# MainBoardR3.net
KiCad netlist of a schematic drawn in EAGLE
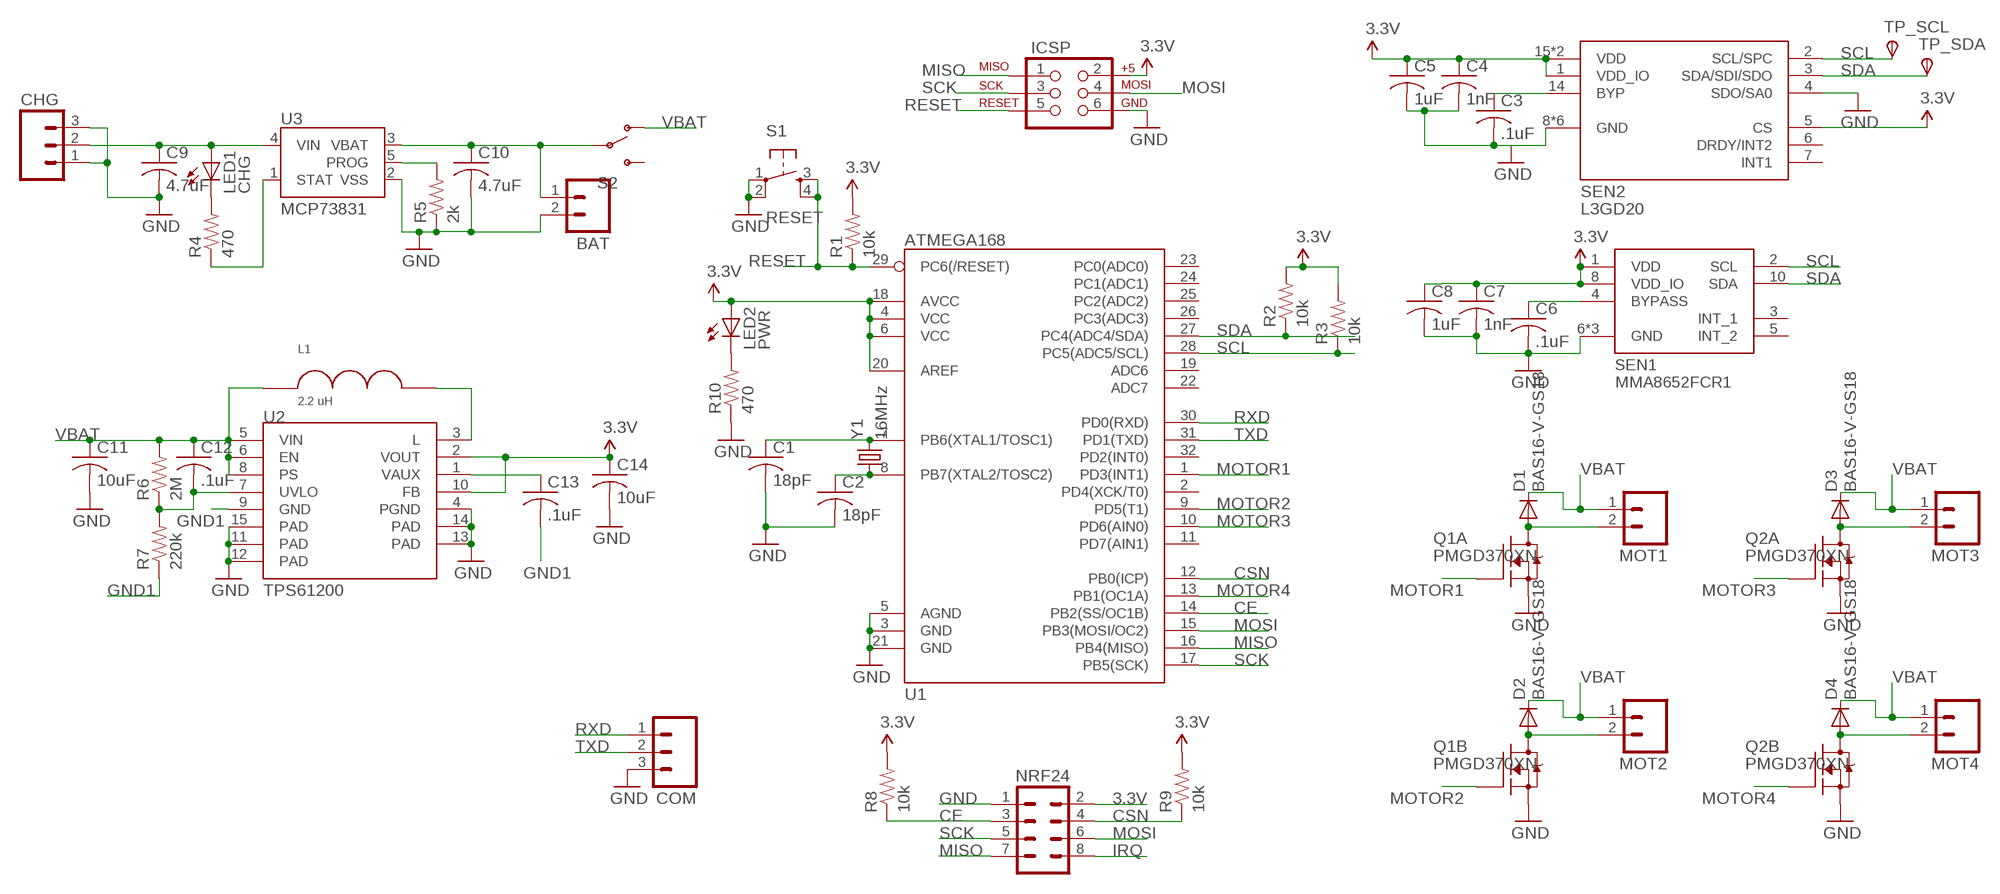
[diagram p0: schematic, sheet 1]

(export (version "E")
  (design (tool "Eeschema 10.0.6"))
  (components
    (comp (ref "BAT")
      (value "M02LOCK_LONGPADS")
      (footprint "eagle-import:1X02_LOCK_LONGPADS")
      (libsource (lib "eagle-import") (part "M02LOCK_LONGPADS"))
    )
    (comp (ref "C1")
      (value "18pF")
      (footprint "eagle-import:C0805")
      (libsource (lib "eagle-import") (part "C-USC0805"))
    )
    (comp (ref "C2")
      (value "18pF")
      (footprint "eagle-import:C0805")
      (libsource (lib "eagle-import") (part "C-USC0805"))
    )
    (comp (ref "C3")
      (value ".1uF")
      (footprint "eagle-import:C0805")
      (libsource (lib "eagle-import") (part "C-USC0805"))
    )
    (comp (ref "C4")
      (value "1nF")
      (footprint "eagle-import:C0805")
      (libsource (lib "eagle-import") (part "C-USC0805"))
    )
    (comp (ref "C5")
      (value "1uF")
      (footprint "eagle-import:C0805")
      (libsource (lib "eagle-import") (part "C-USC0805"))
    )
    (comp (ref "C6")
      (value ".1uF")
      (footprint "eagle-import:C0805")
      (libsource (lib "eagle-import") (part "C-USC0805"))
    )
    (comp (ref "C7")
      (value "1nF")
      (footprint "eagle-import:C0805")
      (libsource (lib "eagle-import") (part "C-USC0805"))
    )
    (comp (ref "C8")
      (value "1uF")
      (footprint "eagle-import:C0805")
      (libsource (lib "eagle-import") (part "C-USC0805"))
    )
    (comp (ref "C9")
      (value "4.7uF")
      (footprint "eagle-import:C0805")
      (libsource (lib "eagle-import") (part "C-USC0805"))
    )
    (comp (ref "C10")
      (value "4.7uF")
      (footprint "eagle-import:C0805")
      (libsource (lib "eagle-import") (part "C-USC0805"))
    )
    (comp (ref "C11")
      (value "10uF")
      (footprint "eagle-import:C0805")
      (libsource (lib "eagle-import") (part "C-USC0805"))
    )
    (comp (ref "C12")
      (value ".1uF")
      (footprint "eagle-import:C0805")
      (libsource (lib "eagle-import") (part "C-USC0805"))
    )
    (comp (ref "C13")
      (value ".1uF")
      (footprint "eagle-import:C0805")
      (libsource (lib "eagle-import") (part "C-USC0805"))
    )
    (comp (ref "C14")
      (value "10uF")
      (footprint "eagle-import:C0805")
      (libsource (lib "eagle-import") (part "C-USC0805"))
    )
    (comp (ref "CHG")
      (value "M03LONGPADS")
      (footprint "eagle-import:1X03_LONGPADS")
      (libsource (lib "eagle-import") (part "M03LONGPADS"))
    )
    (comp (ref "COM")
      (value "M03LONGPADS")
      (footprint "eagle-import:1X03_LONGPADS")
      (libsource (lib "eagle-import") (part "M03LONGPADS"))
    )
    (comp (ref "D1")
      (value "BAS16-V-GS18")
      (footprint "eagle-import:SOT23")
      (libsource (lib "eagle-import") (part "BAS16-V-GS18"))
    )
    (comp (ref "D2")
      (value "BAS16-V-GS18")
      (footprint "eagle-import:SOT23")
      (libsource (lib "eagle-import") (part "BAS16-V-GS18"))
    )
    (comp (ref "D3")
      (value "BAS16-V-GS18")
      (footprint "eagle-import:SOT23")
      (libsource (lib "eagle-import") (part "BAS16-V-GS18"))
    )
    (comp (ref "D4")
      (value "BAS16-V-GS18")
      (footprint "eagle-import:SOT23")
      (libsource (lib "eagle-import") (part "BAS16-V-GS18"))
    )
    (comp (ref "ICSP")
      (value "AVR_SPI_PRG_62X3_LOCK")
      (footprint "eagle-import:2X3_LOCK")
      (libsource (lib "eagle-import") (part "AVR_SPI_PRG_62X3_LOCK"))
    )
    (comp (ref "L1")
      (value "2.2 uH")
      (footprint "eagle-import:2518")
      (libsource (lib "eagle-import") (part "BRHL2518T2R2M"))
    )
    (comp (ref "LED1")
      (value "CHG")
      (footprint "eagle-import:LED-1206")
      (libsource (lib "eagle-import") (part "LED1206"))
    )
    (comp (ref "LED2")
      (value "PWR")
      (footprint "eagle-import:LED-1206")
      (libsource (lib "eagle-import") (part "LED1206"))
    )
    (comp (ref "MOT1")
      (value "M02LOCK_LONGPADS")
      (footprint "eagle-import:1X02_LOCK_LONGPADS")
      (libsource (lib "eagle-import") (part "M02LOCK_LONGPADS"))
    )
    (comp (ref "MOT2")
      (value "M02LOCK_LONGPADS")
      (footprint "eagle-import:1X02_LOCK_LONGPADS")
      (libsource (lib "eagle-import") (part "M02LOCK_LONGPADS"))
    )
    (comp (ref "MOT3")
      (value "M02LOCK_LONGPADS")
      (footprint "eagle-import:1X02_LOCK_LONGPADS")
      (libsource (lib "eagle-import") (part "M02LOCK_LONGPADS"))
    )
    (comp (ref "MOT4")
      (value "M02LOCK_LONGPADS")
      (footprint "eagle-import:1X02_LOCK_LONGPADS")
      (libsource (lib "eagle-import") (part "M02LOCK_LONGPADS"))
    )
    (comp (ref "NRF24")
      (value "M04X2")
      (footprint "eagle-import:2X4")
      (libsource (lib "eagle-import") (part "M04X2"))
    )
    (comp (ref "Q1")
      (value "PMGD370XN")
      (footprint "eagle-import:SOT363_INFINEON")
      (libsource (lib "eagle-import") (part "PMGD370XN"))
    )
    (comp (ref "Q2")
      (value "PMGD370XN")
      (footprint "eagle-import:SOT363_INFINEON")
      (libsource (lib "eagle-import") (part "PMGD370XN"))
    )
    (comp (ref "R1")
      (value "10k")
      (footprint "eagle-import:0805")
      (libsource (lib "eagle-import") (part "RESISTOR0805-RES"))
    )
    (comp (ref "R2")
      (value "10k")
      (footprint "eagle-import:0805")
      (libsource (lib "eagle-import") (part "RESISTOR0805-RES"))
    )
    (comp (ref "R3")
      (value "10k")
      (footprint "eagle-import:0805")
      (libsource (lib "eagle-import") (part "RESISTOR0805-RES"))
    )
    (comp (ref "R4")
      (value "470")
      (footprint "eagle-import:0805")
      (libsource (lib "eagle-import") (part "RESISTOR0805-RES"))
    )
    (comp (ref "R5")
      (value "2k")
      (footprint "eagle-import:0805")
      (libsource (lib "eagle-import") (part "RESISTOR0805-RES"))
    )
    (comp (ref "R6")
      (value "2M")
      (footprint "eagle-import:0805")
      (libsource (lib "eagle-import") (part "RESISTOR0805-RES"))
    )
    (comp (ref "R7")
      (value "220k")
      (footprint "eagle-import:0805")
      (libsource (lib "eagle-import") (part "RESISTOR0805-RES"))
    )
    (comp (ref "R8")
      (value "10k")
      (footprint "eagle-import:0805")
      (libsource (lib "eagle-import") (part "RESISTOR0805-RES"))
    )
    (comp (ref "R9")
      (value "10k")
      (footprint "eagle-import:0805")
      (libsource (lib "eagle-import") (part "RESISTOR0805-RES"))
    )
    (comp (ref "R10")
      (value "470")
      (footprint "eagle-import:0805")
      (libsource (lib "eagle-import") (part "RESISTOR0805-RES"))
    )
    (comp (ref "S1")
      (value "RESET")
      (footprint "eagle-import:TACTILE_SWITCH_SMD")
      (libsource (lib "eagle-import") (part "TAC_SWITCHSMD"))
    )
    (comp (ref "S2")
      (value "SWITCH-SPST-SMD-A")
      (footprint "eagle-import:SWITCH-SPST-SMD-A")
      (libsource (lib "eagle-import") (part "SWITCH-SPST-SMD-A"))
    )
    (comp (ref "SEN1")
      (value "MMA8652FCR1")
      (footprint "eagle-import:10_PIN_DFN")
      (libsource (lib "eagle-import") (part "MMA8652FCR1"))
    )
    (comp (ref "SEN2")
      (value "L3GD20")
      (footprint "eagle-import:LGA-16")
      (libsource (lib "eagle-import") (part "L3GD20"))
    )
    (comp (ref "TP_SCL")
      (value "TPSTP14SQ")
      (footprint "eagle-import:TP14SQ")
      (libsource (lib "eagle-import") (part "TPSTP14SQ"))
    )
    (comp (ref "TP_SDA")
      (value "TPSTP14SQ")
      (footprint "eagle-import:TP14SQ")
      (libsource (lib "eagle-import") (part "TPSTP14SQ"))
    )
    (comp (ref "U1")
      (value "ATMEGA168")
      (footprint "eagle-import:TQFP32-08")
      (libsource (lib "eagle-import") (part "ATMEGA168"))
    )
    (comp (ref "U2")
      (value "TPS61200")
      (footprint "eagle-import:QFN-10_PAD")
      (libsource (lib "eagle-import") (part "TPS61200"))
    )
    (comp (ref "U3")
      (value "MCP73831")
      (footprint "eagle-import:SOT23-5")
      (libsource (lib "eagle-import") (part "MCP73831"))
    )
    (comp (ref "Y1")
      (value "16MHz")
      (footprint "eagle-import:CRYSTAL-SMD-10.5X4.8-2PIN")
      (libsource (lib "eagle-import") (part "CRYSTAL10.5X4.8"))
    )
  )
  (nets
    (net (code "1") (name "/CE") (class "Default")
      (node (ref "NRF24") (pin "3") (pinfunction "3_3") (pintype "passive"))
      (node (ref "R8") (pin "1") (pinfunction "1_1") (pintype "passive"))
      (node (ref "U1") (pin "14") (pinfunction "PB2(SS/OC1B)_14") (pintype "bidirectional"))
    )
    (net (code "2") (name "/CSN") (class "Default")
      (node (ref "NRF24") (pin "4") (pinfunction "4_4") (pintype "passive"))
      (node (ref "R9") (pin "1") (pinfunction "1_1") (pintype "passive"))
      (node (ref "U1") (pin "12") (pinfunction "PB0(ICP)_12") (pintype "bidirectional"))
    )
    (net (code "3") (name "/GND1") (class "Default")
      (node (ref "C13") (pin "2") (pinfunction "2_2") (pintype "passive"))
      (node (ref "R7") (pin "1") (pinfunction "1_1") (pintype "passive"))
      (node (ref "U2") (pin "9") (pinfunction "GND_9") (pintype "power_in"))
    )
    (net (code "4") (name "/IRQ") (class "Default")
      (node (ref "NRF24") (pin "8") (pinfunction "8_8") (pintype "passive"))
    )
    (net (code "5") (name "/MISO") (class "Default")
      (node (ref "ICSP") (pin "1") (pinfunction "1_1") (pintype "passive"))
      (node (ref "NRF24") (pin "7") (pinfunction "7_7") (pintype "passive"))
      (node (ref "U1") (pin "16") (pinfunction "PB4(MISO)_16") (pintype "bidirectional"))
    )
    (net (code "6") (name "/MOSI") (class "Default")
      (node (ref "ICSP") (pin "4") (pinfunction "4_4") (pintype "passive"))
      (node (ref "NRF24") (pin "6") (pinfunction "6_6") (pintype "passive"))
      (node (ref "U1") (pin "15") (pinfunction "PB3(MOSI/OC2)_15") (pintype "bidirectional"))
    )
    (net (code "7") (name "/MOTOR1") (class "Default")
      (node (ref "Q1") (pin "2") (pinfunction "G_2") (pintype "passive"))
      (node (ref "U1") (pin "1") (pinfunction "PD3(INT1)_1") (pintype "bidirectional"))
    )
    (net (code "8") (name "/MOTOR2") (class "Default")
      (node (ref "Q1") (pin "5") (pinfunction "G_5") (pintype "passive"))
      (node (ref "U1") (pin "9") (pinfunction "PD5(T1)_9") (pintype "bidirectional"))
    )
    (net (code "9") (name "/MOTOR3") (class "Default")
      (node (ref "Q2") (pin "2") (pinfunction "G_2") (pintype "passive"))
      (node (ref "U1") (pin "10") (pinfunction "PD6(AIN0)_10") (pintype "bidirectional"))
    )
    (net (code "10") (name "/MOTOR4") (class "Default")
      (node (ref "Q2") (pin "5") (pinfunction "G_5") (pintype "passive"))
      (node (ref "U1") (pin "13") (pinfunction "PB1(OC1A)_13") (pintype "bidirectional"))
    )
    (net (code "11") (name "/RESET") (class "Default")
      (node (ref "ICSP") (pin "5") (pinfunction "5_5") (pintype "passive"))
      (node (ref "R1") (pin "1") (pinfunction "1_1") (pintype "passive"))
      (node (ref "S1") (pin "3") (pinfunction "3_3") (pintype "passive"))
      (node (ref "S1") (pin "4") (pinfunction "4_4") (pintype "passive"))
      (node (ref "U1") (pin "29") (pinfunction "PC6(/RESET)_29") (pintype "bidirectional"))
    )
    (net (code "12") (name "/RXD") (class "Default")
      (node (ref "COM") (pin "1") (pinfunction "1_1") (pintype "passive"))
      (node (ref "U1") (pin "30") (pinfunction "PD0(RXD)_30") (pintype "bidirectional"))
    )
    (net (code "13") (name "/SCK") (class "Default")
      (node (ref "ICSP") (pin "3") (pinfunction "3_3") (pintype "passive"))
      (node (ref "NRF24") (pin "5") (pinfunction "5_5") (pintype "passive"))
      (node (ref "U1") (pin "17") (pinfunction "PB5(SCK)_17") (pintype "bidirectional"))
    )
    (net (code "14") (name "/SCL") (class "Default")
      (node (ref "R3") (pin "1") (pinfunction "1_1") (pintype "passive"))
      (node (ref "SEN1") (pin "2") (pinfunction "SCL_2") (pintype "bidirectional"))
      (node (ref "SEN2") (pin "2") (pinfunction "SCL/SPC_2") (pintype "bidirectional"))
      (node (ref "TP_SCL") (pin "TP") (pinfunction "PP_TP") (pintype "input"))
      (node (ref "U1") (pin "28") (pinfunction "PC5(ADC5/SCL)_28") (pintype "bidirectional"))
    )
    (net (code "15") (name "/SDA") (class "Default")
      (node (ref "R2") (pin "1") (pinfunction "1_1") (pintype "passive"))
      (node (ref "SEN1") (pin "10") (pinfunction "SDA_10") (pintype "bidirectional"))
      (node (ref "SEN2") (pin "3") (pinfunction "SDA/SDI/SDO_3") (pintype "bidirectional"))
      (node (ref "TP_SDA") (pin "TP") (pinfunction "PP_TP") (pintype "input"))
      (node (ref "U1") (pin "27") (pinfunction "PC4(ADC4/SDA)_27") (pintype "bidirectional"))
    )
    (net (code "16") (name "/TXD") (class "Default")
      (node (ref "COM") (pin "2") (pinfunction "2_2") (pintype "passive"))
      (node (ref "U1") (pin "31") (pinfunction "PD1(TXD)_31") (pintype "bidirectional"))
    )
    (net (code "17") (name "/VBAT") (class "Default")
      (node (ref "C11") (pin "1") (pinfunction "1_1") (pintype "passive"))
      (node (ref "C12") (pin "1") (pinfunction "1_1") (pintype "passive"))
      (node (ref "D1") (pin "3") (pinfunction "C_3") (pintype "passive"))
      (node (ref "D2") (pin "3") (pinfunction "C_3") (pintype "passive"))
      (node (ref "D3") (pin "3") (pinfunction "C_3") (pintype "passive"))
      (node (ref "D4") (pin "3") (pinfunction "C_3") (pintype "passive"))
      (node (ref "L1") (pin "P$1") (pinfunction "1_P$1") (pintype "bidirectional"))
      (node (ref "MOT1") (pin "1") (pinfunction "1_1") (pintype "passive"))
      (node (ref "MOT2") (pin "1") (pinfunction "1_1") (pintype "passive"))
      (node (ref "MOT3") (pin "1") (pinfunction "1_1") (pintype "passive"))
      (node (ref "MOT4") (pin "1") (pinfunction "1_1") (pintype "passive"))
      (node (ref "R6") (pin "2") (pinfunction "2_2") (pintype "passive"))
      (node (ref "S2") (pin "1") (pinfunction "O_1") (pintype "passive"))
      (node (ref "U2") (pin "5") (pinfunction "VIN_5") (pintype "power_in"))
      (node (ref "U2") (pin "6") (pinfunction "EN_6") (pintype "input"))
      (node (ref "U2") (pin "8") (pinfunction "PS_8") (pintype "input"))
    )
    (net (code "18") (name "3.3V") (class "Default")
      (node (ref "C14") (pin "1") (pinfunction "1_1") (pintype "passive"))
      (node (ref "C4") (pin "1") (pinfunction "1_1") (pintype "passive"))
      (node (ref "C5") (pin "1") (pinfunction "1_1") (pintype "passive"))
      (node (ref "C7") (pin "1") (pinfunction "1_1") (pintype "passive"))
      (node (ref "C8") (pin "1") (pinfunction "1_1") (pintype "passive"))
      (node (ref "ICSP") (pin "2") (pinfunction "2_2") (pintype "passive"))
      (node (ref "LED2") (pin "A") (pinfunction "A_A") (pintype "passive"))
      (node (ref "NRF24") (pin "2") (pinfunction "2_2") (pintype "passive"))
      (node (ref "R1") (pin "2") (pinfunction "2_2") (pintype "passive"))
      (node (ref "R2") (pin "2") (pinfunction "2_2") (pintype "passive"))
      (node (ref "R3") (pin "2") (pinfunction "2_2") (pintype "passive"))
      (node (ref "R8") (pin "2") (pinfunction "2_2") (pintype "passive"))
      (node (ref "R9") (pin "2") (pinfunction "2_2") (pintype "passive"))
      (node (ref "SEN1") (pin "1") (pinfunction "VDD_1") (pintype "bidirectional"))
      (node (ref "SEN1") (pin "8") (pinfunction "VDD_IO_8") (pintype "bidirectional"))
      (node (ref "SEN2") (pin "1") (pinfunction "VDD_IO_1") (pintype "bidirectional"))
      (node (ref "SEN2") (pin "15") (pinfunction "VDD_15") (pintype "bidirectional"))
      (node (ref "SEN2") (pin "16") (pinfunction "VDD_16") (pintype "bidirectional"))
      (node (ref "SEN2") (pin "5") (pinfunction "CS_5") (pintype "bidirectional"))
      (node (ref "U1") (pin "18") (pinfunction "AVCC_18") (pintype "bidirectional"))
      (node (ref "U1") (pin "20") (pinfunction "AREF_20") (pintype "bidirectional"))
      (node (ref "U1") (pin "4") (pinfunction "VCC_4") (pintype "bidirectional"))
      (node (ref "U1") (pin "6") (pinfunction "VCC_6") (pintype "bidirectional"))
      (node (ref "U2") (pin "10") (pinfunction "FB_10") (pintype "passive"))
      (node (ref "U2") (pin "2") (pinfunction "VOUT_2") (pintype "passive"))
    )
    (net (code "19") (name "GND") (class "Default")
      (node (ref "BAT") (pin "2") (pinfunction "2_2") (pintype "passive"))
      (node (ref "C1") (pin "2") (pinfunction "2_2") (pintype "passive"))
      (node (ref "C10") (pin "2") (pinfunction "2_2") (pintype "passive"))
      (node (ref "C11") (pin "2") (pinfunction "2_2") (pintype "passive"))
      (node (ref "C14") (pin "2") (pinfunction "2_2") (pintype "passive"))
      (node (ref "C2") (pin "2") (pinfunction "2_2") (pintype "passive"))
      (node (ref "C3") (pin "2") (pinfunction "2_2") (pintype "passive"))
      (node (ref "C4") (pin "2") (pinfunction "2_2") (pintype "passive"))
      (node (ref "C5") (pin "2") (pinfunction "2_2") (pintype "passive"))
      (node (ref "C6") (pin "2") (pinfunction "2_2") (pintype "passive"))
      (node (ref "C7") (pin "2") (pinfunction "2_2") (pintype "passive"))
      (node (ref "C8") (pin "2") (pinfunction "2_2") (pintype "passive"))
      (node (ref "C9") (pin "2") (pinfunction "2_2") (pintype "passive"))
      (node (ref "CHG") (pin "1") (pinfunction "1_1") (pintype "passive"))
      (node (ref "CHG") (pin "3") (pinfunction "3_3") (pintype "passive"))
      (node (ref "COM") (pin "3") (pinfunction "3_3") (pintype "passive"))
      (node (ref "ICSP") (pin "6") (pinfunction "6_6") (pintype "passive"))
      (node (ref "NRF24") (pin "1") (pinfunction "1_1") (pintype "passive"))
      (node (ref "Q1") (pin "1") (pinfunction "S_1") (pintype "passive"))
      (node (ref "Q1") (pin "4") (pinfunction "S_4") (pintype "passive"))
      (node (ref "Q2") (pin "1") (pinfunction "S_1") (pintype "passive"))
      (node (ref "Q2") (pin "4") (pinfunction "S_4") (pintype "passive"))
      (node (ref "R10") (pin "1") (pinfunction "1_1") (pintype "passive"))
      (node (ref "R5") (pin "1") (pinfunction "1_1") (pintype "passive"))
      (node (ref "S1") (pin "1") (pinfunction "1_1") (pintype "passive"))
      (node (ref "S1") (pin "2") (pinfunction "2_2") (pintype "passive"))
      (node (ref "SEN1") (pin "6") (pinfunction "GND_6") (pintype "bidirectional"))
      (node (ref "SEN1") (pin "7") (pinfunction "GND_7") (pintype "bidirectional"))
      (node (ref "SEN1") (pin "9") (pinfunction "GND_9") (pintype "bidirectional"))
      (node (ref "SEN2") (pin "10") (pinfunction "GND_10") (pintype "bidirectional"))
      (node (ref "SEN2") (pin "11") (pinfunction "GND_11") (pintype "bidirectional"))
      (node (ref "SEN2") (pin "12") (pinfunction "GND_12") (pintype "bidirectional"))
      (node (ref "SEN2") (pin "13") (pinfunction "GND_13") (pintype "bidirectional"))
      (node (ref "SEN2") (pin "4") (pinfunction "SDO/SA0_4") (pintype "bidirectional"))
      (node (ref "SEN2") (pin "8") (pinfunction "GND_8") (pintype "bidirectional"))
      (node (ref "SEN2") (pin "9") (pinfunction "GND_9") (pintype "bidirectional"))
      (node (ref "U1") (pin "21") (pinfunction "GND_21") (pintype "bidirectional"))
      (node (ref "U1") (pin "3") (pinfunction "GND_3") (pintype "bidirectional"))
      (node (ref "U1") (pin "5") (pinfunction "AGND_5") (pintype "bidirectional"))
      (node (ref "U2") (pin "11") (pinfunction "PAD_11") (pintype "power_in"))
      (node (ref "U2") (pin "12") (pinfunction "PAD_12") (pintype "power_in"))
      (node (ref "U2") (pin "13") (pinfunction "PAD_13") (pintype "power_in"))
      (node (ref "U2") (pin "14") (pinfunction "PAD_14") (pintype "power_in"))
      (node (ref "U2") (pin "15") (pinfunction "PAD_15") (pintype "power_in"))
      (node (ref "U2") (pin "4") (pinfunction "PGND_4") (pintype "power_in"))
      (node (ref "U3") (pin "2") (pinfunction "VSS_2") (pintype "power_in"))
    )
    (net (code "20") (name "Net-(D1-A)") (class "Default")
      (node (ref "D1") (pin "1") (pinfunction "A_1") (pintype "passive"))
      (node (ref "MOT1") (pin "2") (pinfunction "2_2") (pintype "passive"))
      (node (ref "Q1") (pin "6") (pinfunction "D_6") (pintype "passive"))
    )
    (net (code "21") (name "Net-(D2-A)") (class "Default")
      (node (ref "D2") (pin "1") (pinfunction "A_1") (pintype "passive"))
      (node (ref "MOT2") (pin "2") (pinfunction "2_2") (pintype "passive"))
      (node (ref "Q1") (pin "3") (pinfunction "D_3") (pintype "passive"))
    )
    (net (code "22") (name "Net-(D3-A)") (class "Default")
      (node (ref "D3") (pin "1") (pinfunction "A_1") (pintype "passive"))
      (node (ref "MOT3") (pin "2") (pinfunction "2_2") (pintype "passive"))
      (node (ref "Q2") (pin "6") (pinfunction "D_6") (pintype "passive"))
    )
    (net (code "23") (name "Net-(D4-A)") (class "Default")
      (node (ref "D4") (pin "1") (pinfunction "A_1") (pintype "passive"))
      (node (ref "MOT4") (pin "2") (pinfunction "2_2") (pintype "passive"))
      (node (ref "Q2") (pin "3") (pinfunction "D_3") (pintype "passive"))
    )
    (net (code "24") (name "Net-(L1-2)") (class "Default")
      (node (ref "L1") (pin "P$2") (pinfunction "2_P$2") (pintype "bidirectional"))
      (node (ref "U2") (pin "3") (pinfunction "L_3") (pintype "passive"))
    )
    (net (code "25") (name "Net-(LED1-PadC)") (class "Default")
      (node (ref "LED1") (pin "C") (pinfunction "C_C") (pintype "passive"))
      (node (ref "R4") (pin "2") (pinfunction "2_2") (pintype "passive"))
    )
    (net (code "26") (name "Net-(LED2-PadC)") (class "Default")
      (node (ref "LED2") (pin "C") (pinfunction "C_C") (pintype "passive"))
      (node (ref "R10") (pin "2") (pinfunction "2_2") (pintype "passive"))
    )
    (net (code "27") (name "Net-(S2-P)") (class "Default")
      (node (ref "BAT") (pin "1") (pinfunction "1_1") (pintype "passive"))
      (node (ref "C10") (pin "1") (pinfunction "1_1") (pintype "passive"))
      (node (ref "S2") (pin "2") (pinfunction "P_2") (pintype "passive"))
      (node (ref "U3") (pin "3") (pinfunction "VBAT_3") (pintype "power_in"))
    )
    (net (code "28") (name "Net-(SEN1-BYPASS)") (class "Default")
      (node (ref "C6") (pin "1") (pinfunction "1_1") (pintype "passive"))
      (node (ref "SEN1") (pin "4") (pinfunction "BYPASS_4") (pintype "bidirectional"))
    )
    (net (code "29") (name "Net-(SEN2-BYP)") (class "Default")
      (node (ref "C3") (pin "1") (pinfunction "1_1") (pintype "passive"))
      (node (ref "SEN2") (pin "14") (pinfunction "BYP_14") (pintype "bidirectional"))
    )
    (net (code "30") (name "Net-(U1-PB6(XTAL1{slash}TOSC1))") (class "Default")
      (node (ref "C1") (pin "1") (pinfunction "1_1") (pintype "passive"))
      (node (ref "U1") (pin "7") (pinfunction "PB6(XTAL1/TOSC1)_7") (pintype "bidirectional"))
      (node (ref "Y1") (pin "P$2") (pinfunction "2_P$2") (pintype "passive"))
    )
    (net (code "31") (name "Net-(U1-PB7(XTAL2{slash}TOSC2))") (class "Default")
      (node (ref "C2") (pin "1") (pinfunction "1_1") (pintype "passive"))
      (node (ref "U1") (pin "8") (pinfunction "PB7(XTAL2/TOSC2)_8") (pintype "bidirectional"))
      (node (ref "Y1") (pin "P$1") (pinfunction "1_P$1") (pintype "passive"))
    )
    (net (code "32") (name "Net-(U2-UVLO)") (class "Default")
      (node (ref "C12") (pin "2") (pinfunction "2_2") (pintype "passive"))
      (node (ref "R6") (pin "1") (pinfunction "1_1") (pintype "passive"))
      (node (ref "R7") (pin "2") (pinfunction "2_2") (pintype "passive"))
      (node (ref "U2") (pin "7") (pinfunction "UVLO_7") (pintype "passive"))
    )
    (net (code "33") (name "Net-(U2-VAUX)") (class "Default")
      (node (ref "C13") (pin "1") (pinfunction "1_1") (pintype "passive"))
      (node (ref "U2") (pin "1") (pinfunction "VAUX_1") (pintype "passive"))
    )
    (net (code "34") (name "Net-(U3-PROG)") (class "Default")
      (node (ref "R5") (pin "2") (pinfunction "2_2") (pintype "passive"))
      (node (ref "U3") (pin "5") (pinfunction "PROG_5") (pintype "input"))
    )
    (net (code "35") (name "Net-(U3-STAT)") (class "Default")
      (node (ref "R4") (pin "1") (pinfunction "1_1") (pintype "passive"))
      (node (ref "U3") (pin "1") (pinfunction "STAT_1") (pintype "output"))
    )
    (net (code "36") (name "Net-(U3-VIN)") (class "Default")
      (node (ref "C9") (pin "1") (pinfunction "1_1") (pintype "passive"))
      (node (ref "CHG") (pin "2") (pinfunction "2_2") (pintype "passive"))
      (node (ref "LED1") (pin "A") (pinfunction "A_A") (pintype "passive"))
      (node (ref "U3") (pin "4") (pinfunction "VIN_4") (pintype "power_in"))
    )
    (net (code "37") (name "unconnected-(S2-S-Pad3)") (class "Default")
      (node (ref "S2") (pin "3") (pinfunction "S_3") (pintype "passive"))
    )
    (net (code "38") (name "unconnected-(SEN1-INT_1-Pad3)") (class "Default")
      (node (ref "SEN1") (pin "3") (pinfunction "INT_1_3") (pintype "bidirectional"))
    )
    (net (code "39") (name "unconnected-(SEN1-INT_2-Pad5)") (class "Default")
      (node (ref "SEN1") (pin "5") (pinfunction "INT_2_5") (pintype "bidirectional"))
    )
    (net (code "40") (name "unconnected-(SEN2-DRDY{slash}INT2-Pad6)") (class "Default")
      (node (ref "SEN2") (pin "6") (pinfunction "DRDY/INT2_6") (pintype "bidirectional"))
    )
    (net (code "41") (name "unconnected-(SEN2-INT1-Pad7)") (class "Default")
      (node (ref "SEN2") (pin "7") (pinfunction "INT1_7") (pintype "bidirectional"))
    )
    (net (code "42") (name "unconnected-(U1-ADC6-Pad19)") (class "Default")
      (node (ref "U1") (pin "19") (pinfunction "ADC6_19") (pintype "bidirectional"))
    )
    (net (code "43") (name "unconnected-(U1-ADC7-Pad22)") (class "Default")
      (node (ref "U1") (pin "22") (pinfunction "ADC7_22") (pintype "bidirectional"))
    )
    (net (code "44") (name "unconnected-(U1-PC0(ADC0)-Pad23)") (class "Default")
      (node (ref "U1") (pin "23") (pinfunction "PC0(ADC0)_23") (pintype "bidirectional"))
    )
    (net (code "45") (name "unconnected-(U1-PC1(ADC1)-Pad24)") (class "Default")
      (node (ref "U1") (pin "24") (pinfunction "PC1(ADC1)_24") (pintype "bidirectional"))
    )
    (net (code "46") (name "unconnected-(U1-PC2(ADC2)-Pad25)") (class "Default")
      (node (ref "U1") (pin "25") (pinfunction "PC2(ADC2)_25") (pintype "bidirectional"))
    )
    (net (code "47") (name "unconnected-(U1-PC3(ADC3)-Pad26)") (class "Default")
      (node (ref "U1") (pin "26") (pinfunction "PC3(ADC3)_26") (pintype "bidirectional"))
    )
    (net (code "48") (name "unconnected-(U1-PD2(INT0)-Pad32)") (class "Default")
      (node (ref "U1") (pin "32") (pinfunction "PD2(INT0)_32") (pintype "bidirectional"))
    )
    (net (code "49") (name "unconnected-(U1-PD4(XCK{slash}T0)-Pad2)") (class "Default")
      (node (ref "U1") (pin "2") (pinfunction "PD4(XCK/T0)_2") (pintype "bidirectional"))
    )
    (net (code "50") (name "unconnected-(U1-PD7(AIN1)-Pad11)") (class "Default")
      (node (ref "U1") (pin "11") (pinfunction "PD7(AIN1)_11") (pintype "bidirectional"))
    )
  )
)
